# BMSNodeV1.net
KiCad netlist of a schematic drawn in EAGLE
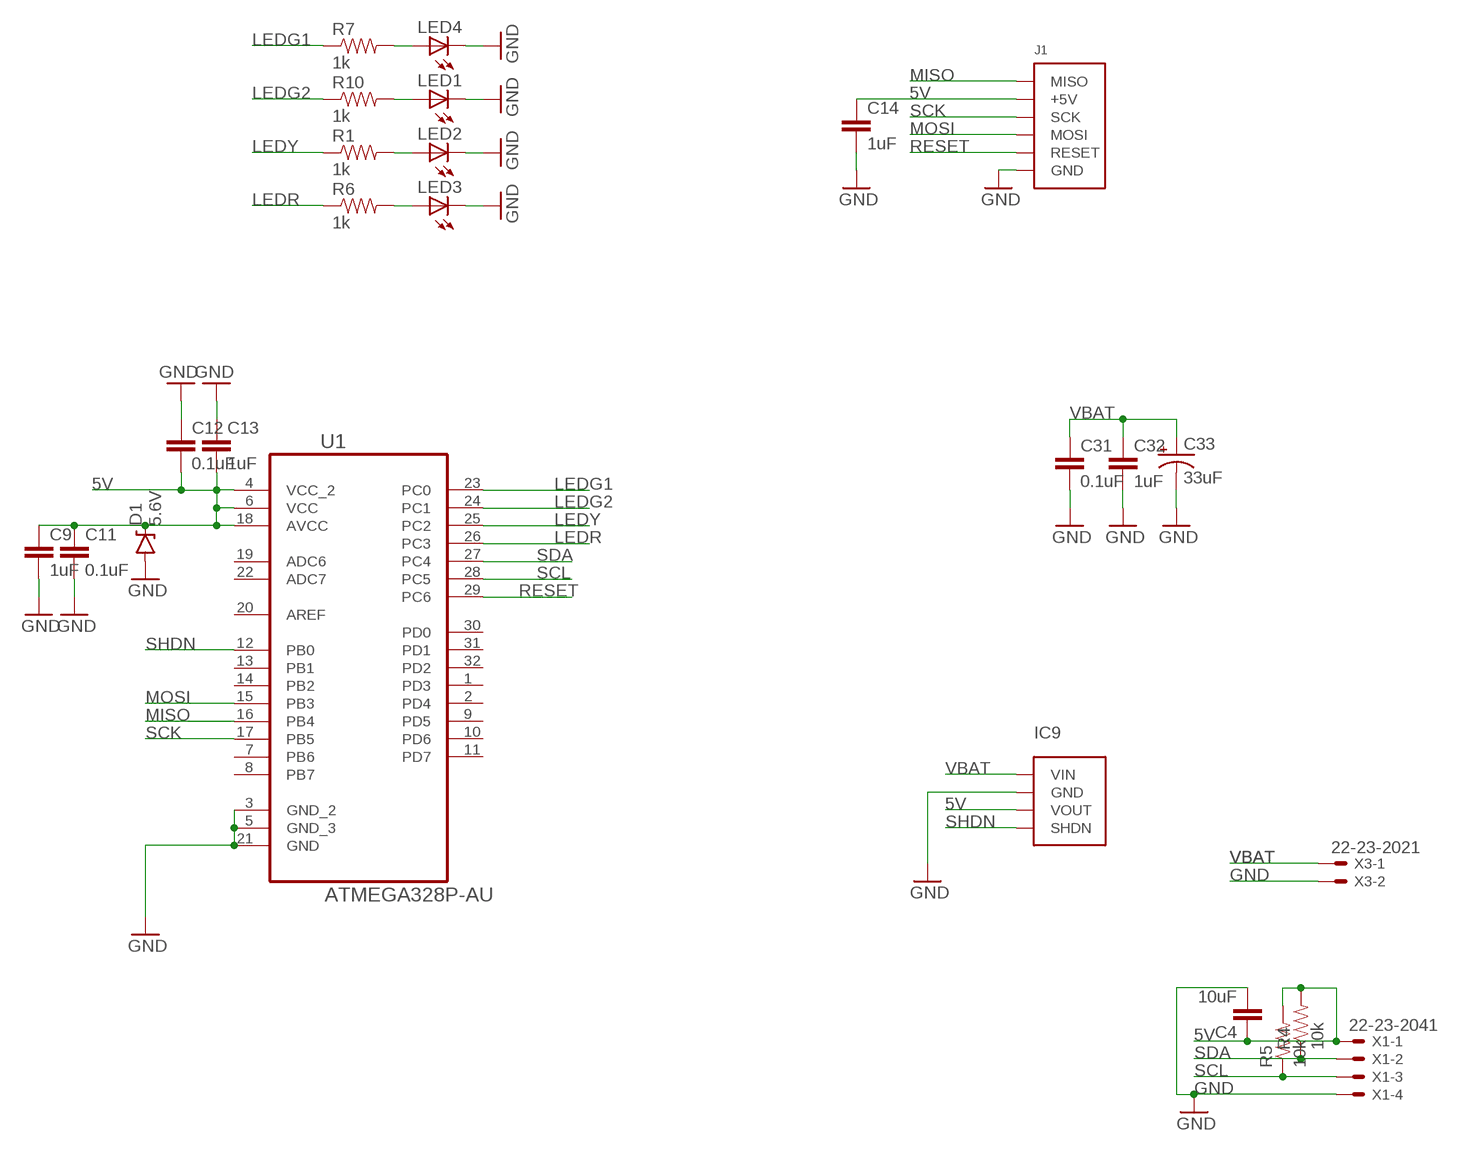
[diagram p0: schematic, sheet 1]

(export (version "E")
  (design (tool "Eeschema 10.0.6"))
  (components
    (comp (ref "C4")
      (value "10uF")
      (footprint "eagle-import:0805-CAP")
      (libsource (lib "eagle-import") (part "10UF10V10%(0805)"))
    )
    (comp (ref "C9")
      (value "1uF")
      (footprint "eagle-import:0805-CAP")
      (libsource (lib "eagle-import") (part "0.33UF-50V-10%(0805)"))
    )
    (comp (ref "C11")
      (value "0.1uF")
      (footprint "eagle-import:0805-CAP")
      (libsource (lib "eagle-import") (part "0.33UF-50V-10%(0805)"))
    )
    (comp (ref "C12")
      (value "0.1uF")
      (footprint "eagle-import:0805-CAP")
      (libsource (lib "eagle-import") (part "0.33UF-50V-10%(0805)"))
    )
    (comp (ref "C13")
      (value "1uF")
      (footprint "eagle-import:0805-CAP")
      (libsource (lib "eagle-import") (part "0.33UF-50V-10%(0805)"))
    )
    (comp (ref "C14")
      (value "1uF")
      (footprint "eagle-import:0805-CAP")
      (libsource (lib "eagle-import") (part "0.33UF-50V-10%(0805)"))
    )
    (comp (ref "C31")
      (value "0.1uF")
      (footprint "eagle-import:0805-CAP")
      (libsource (lib "eagle-import") (part "0.33UF-50V-10%(0805)"))
    )
    (comp (ref "C32")
      (value "1uF")
      (footprint "eagle-import:0805-CAP")
      (libsource (lib "eagle-import") (part "0.33UF-50V-10%(0805)"))
    )
    (comp (ref "C33")
      (value "33uF")
      (footprint "eagle-import:NIPPON_F80")
      (libsource (lib "eagle-import") (part "CAP_POLF80"))
    )
    (comp (ref "D1")
      (value "5.6V")
      (footprint "eagle-import:SOD-323")
      (libsource (lib "eagle-import") (part "DIODE-ZENER5.6V"))
    )
    (comp (ref "IC9")
      (value "5VBUCK_DANNY_CUSTOM_PCB")
      (footprint "eagle-import:4PIN_.1'")
      (libsource (lib "eagle-import") (part "5VBUCK_DANNY_CUSTOM_PCB"))
    )
    (comp (ref "J1")
      (value "ISPHEADER")
      (footprint "eagle-import:2X3PIN_.1'")
      (libsource (lib "eagle-import") (part "ISPHEADER"))
    )
    (comp (ref "LED1")
      (value "LEDCHIPLED_0805")
      (footprint "eagle-import:CHIPLED_0805")
      (libsource (lib "eagle-import") (part "LEDCHIPLED_0805"))
    )
    (comp (ref "LED2")
      (value "LEDCHIPLED_0805")
      (footprint "eagle-import:CHIPLED_0805")
      (libsource (lib "eagle-import") (part "LEDCHIPLED_0805"))
    )
    (comp (ref "LED3")
      (value "LEDCHIPLED_0805")
      (footprint "eagle-import:CHIPLED_0805")
      (libsource (lib "eagle-import") (part "LEDCHIPLED_0805"))
    )
    (comp (ref "LED4")
      (value "LEDCHIPLED_0805")
      (footprint "eagle-import:CHIPLED_0805")
      (libsource (lib "eagle-import") (part "LEDCHIPLED_0805"))
    )
    (comp (ref "R1")
      (value "1k")
      (footprint "eagle-import:0805")
      (libsource (lib "eagle-import") (part "0.3OHM-1/8W-1%(0805)"))
    )
    (comp (ref "R4")
      (value "10k")
      (footprint "eagle-import:0805")
      (libsource (lib "eagle-import") (part "0.3OHM-1/8W-1%(0805)"))
    )
    (comp (ref "R5")
      (value "10k")
      (footprint "eagle-import:0805")
      (libsource (lib "eagle-import") (part "0.3OHM-1/8W-1%(0805)"))
    )
    (comp (ref "R6")
      (value "1k")
      (footprint "eagle-import:0805")
      (libsource (lib "eagle-import") (part "0.3OHM-1/8W-1%(0805)"))
    )
    (comp (ref "R7")
      (value "1k")
      (footprint "eagle-import:0805")
      (libsource (lib "eagle-import") (part "0.3OHM-1/8W-1%(0805)"))
    )
    (comp (ref "R10")
      (value "1k")
      (footprint "eagle-import:0805")
      (libsource (lib "eagle-import") (part "0.3OHM-1/8W-1%(0805)"))
    )
    (comp (ref "U1")
      (value "ATMEGA328P-AU")
      (footprint "eagle-import:QFP80P900X900X120-32N")
      (libsource (lib "eagle-import") (part "ATMEGA328P-AU"))
    )
    (comp (ref "X1")
      (value "22-23-2041")
      (footprint "eagle-import:22-23-2041")
      (fields (field (name "MF") "MOLEX"))
      (libsource (lib "eagle-import") (part "22-23-2041"))
    )
    (comp (ref "X3")
      (value "22-23-2021")
      (footprint "eagle-import:22-23-2021")
      (fields (field (name "MF") "MOLEX"))
      (libsource (lib "eagle-import") (part "22-23-2021"))
    )
  )
  (nets
    (net (code "1") (name "/5V") (class "Default")
      (node (ref "C11") (pin "1") (pinfunction "1_1") (pintype "passive"))
      (node (ref "C12") (pin "2") (pinfunction "2_2") (pintype "passive"))
      (node (ref "C13") (pin "2") (pinfunction "2_2") (pintype "passive"))
      (node (ref "C14") (pin "1") (pinfunction "1_1") (pintype "passive"))
      (node (ref "C4") (pin "1") (pinfunction "1_1") (pintype "passive"))
      (node (ref "C9") (pin "1") (pinfunction "1_1") (pintype "passive"))
      (node (ref "D1") (pin "C") (pinfunction "C_C") (pintype "passive"))
      (node (ref "IC9") (pin "P$3") (pinfunction "VOUT_P$3") (pintype "bidirectional"))
      (node (ref "J1") (pin "P$2") (pinfunction "+5V_P$2") (pintype "bidirectional"))
      (node (ref "R4") (pin "2") (pinfunction "2_2") (pintype "passive"))
      (node (ref "R5") (pin "2") (pinfunction "2_2") (pintype "passive"))
      (node (ref "U1") (pin "18") (pinfunction "AVCC_18") (pintype "power_in"))
      (node (ref "U1") (pin "4") (pinfunction "VCC_2_4") (pintype "power_in"))
      (node (ref "U1") (pin "6") (pinfunction "VCC_6") (pintype "power_in"))
      (node (ref "X1") (pin "1") (pinfunction "S_1") (pintype "passive"))
    )
    (net (code "2") (name "/LEDG1") (class "Default")
      (node (ref "R7") (pin "1") (pinfunction "1_1") (pintype "passive"))
      (node (ref "U1") (pin "23") (pinfunction "PC0_23") (pintype "bidirectional"))
    )
    (net (code "3") (name "/LEDG2") (class "Default")
      (node (ref "R10") (pin "1") (pinfunction "1_1") (pintype "passive"))
      (node (ref "U1") (pin "24") (pinfunction "PC1_24") (pintype "bidirectional"))
    )
    (net (code "4") (name "/LEDR") (class "Default")
      (node (ref "R6") (pin "1") (pinfunction "1_1") (pintype "passive"))
      (node (ref "U1") (pin "26") (pinfunction "PC3_26") (pintype "bidirectional"))
    )
    (net (code "5") (name "/LEDY") (class "Default")
      (node (ref "R1") (pin "1") (pinfunction "1_1") (pintype "passive"))
      (node (ref "U1") (pin "25") (pinfunction "PC2_25") (pintype "bidirectional"))
    )
    (net (code "6") (name "/MISO") (class "Default")
      (node (ref "J1") (pin "P$1") (pinfunction "MISO_P$1") (pintype "bidirectional"))
      (node (ref "U1") (pin "16") (pinfunction "PB4_16") (pintype "bidirectional"))
    )
    (net (code "7") (name "/MOSI") (class "Default")
      (node (ref "J1") (pin "P$4") (pinfunction "MOSI_P$4") (pintype "bidirectional"))
      (node (ref "U1") (pin "15") (pinfunction "PB3_15") (pintype "bidirectional"))
    )
    (net (code "8") (name "/RESET") (class "Default")
      (node (ref "J1") (pin "P$5") (pinfunction "RESET_P$5") (pintype "bidirectional"))
      (node (ref "U1") (pin "29") (pinfunction "PC6_29") (pintype "bidirectional"))
    )
    (net (code "9") (name "/SCK") (class "Default")
      (node (ref "J1") (pin "P$3") (pinfunction "SCK_P$3") (pintype "bidirectional"))
      (node (ref "U1") (pin "17") (pinfunction "PB5_17") (pintype "bidirectional"))
    )
    (net (code "10") (name "/SCL") (class "Default")
      (node (ref "R5") (pin "1") (pinfunction "1_1") (pintype "passive"))
      (node (ref "U1") (pin "28") (pinfunction "PC5_28") (pintype "bidirectional"))
      (node (ref "X1") (pin "3") (pinfunction "S_3") (pintype "passive"))
    )
    (net (code "11") (name "/SDA") (class "Default")
      (node (ref "R4") (pin "1") (pinfunction "1_1") (pintype "passive"))
      (node (ref "U1") (pin "27") (pinfunction "PC4_27") (pintype "bidirectional"))
      (node (ref "X1") (pin "2") (pinfunction "S_2") (pintype "passive"))
    )
    (net (code "12") (name "/SHDN") (class "Default")
      (node (ref "IC9") (pin "P$4") (pinfunction "SHDN_P$4") (pintype "bidirectional"))
      (node (ref "U1") (pin "12") (pinfunction "PB0_12") (pintype "bidirectional"))
    )
    (net (code "13") (name "/VBAT") (class "Default")
      (node (ref "C31") (pin "1") (pinfunction "1_1") (pintype "passive"))
      (node (ref "C32") (pin "1") (pinfunction "1_1") (pintype "passive"))
      (node (ref "C33") (pin "+") (pinfunction "+_+") (pintype "passive"))
      (node (ref "IC9") (pin "P$1") (pinfunction "VIN_P$1") (pintype "bidirectional"))
      (node (ref "X3") (pin "1") (pinfunction "S_1") (pintype "passive"))
    )
    (net (code "14") (name "GND") (class "Default")
      (node (ref "C11") (pin "2") (pinfunction "2_2") (pintype "passive"))
      (node (ref "C12") (pin "1") (pinfunction "1_1") (pintype "passive"))
      (node (ref "C13") (pin "1") (pinfunction "1_1") (pintype "passive"))
      (node (ref "C14") (pin "2") (pinfunction "2_2") (pintype "passive"))
      (node (ref "C31") (pin "2") (pinfunction "2_2") (pintype "passive"))
      (node (ref "C32") (pin "2") (pinfunction "2_2") (pintype "passive"))
      (node (ref "C33") (pin "-") (pinfunction "-_-") (pintype "passive"))
      (node (ref "C4") (pin "2") (pinfunction "2_2") (pintype "passive"))
      (node (ref "C9") (pin "2") (pinfunction "2_2") (pintype "passive"))
      (node (ref "D1") (pin "A") (pinfunction "A_A") (pintype "passive"))
      (node (ref "IC9") (pin "P$2") (pinfunction "GND_P$2") (pintype "bidirectional"))
      (node (ref "J1") (pin "P$6") (pinfunction "GND_P$6") (pintype "bidirectional"))
      (node (ref "LED1") (pin "C") (pinfunction "C_C") (pintype "passive"))
      (node (ref "LED2") (pin "C") (pinfunction "C_C") (pintype "passive"))
      (node (ref "LED3") (pin "C") (pinfunction "C_C") (pintype "passive"))
      (node (ref "LED4") (pin "C") (pinfunction "C_C") (pintype "passive"))
      (node (ref "U1") (pin "21") (pinfunction "GND_21") (pintype "passive"))
      (node (ref "U1") (pin "3") (pinfunction "GND_2_3") (pintype "passive"))
      (node (ref "U1") (pin "5") (pinfunction "GND_3_5") (pintype "passive"))
      (node (ref "X1") (pin "4") (pinfunction "S_4") (pintype "passive"))
      (node (ref "X3") (pin "2") (pinfunction "S_2") (pintype "passive"))
    )
    (net (code "15") (name "Net-(LED1-PadA)") (class "Default")
      (node (ref "LED1") (pin "A") (pinfunction "A_A") (pintype "passive"))
      (node (ref "R10") (pin "2") (pinfunction "2_2") (pintype "passive"))
    )
    (net (code "16") (name "Net-(LED2-PadA)") (class "Default")
      (node (ref "LED2") (pin "A") (pinfunction "A_A") (pintype "passive"))
      (node (ref "R1") (pin "2") (pinfunction "2_2") (pintype "passive"))
    )
    (net (code "17") (name "Net-(LED3-PadA)") (class "Default")
      (node (ref "LED3") (pin "A") (pinfunction "A_A") (pintype "passive"))
      (node (ref "R6") (pin "2") (pinfunction "2_2") (pintype "passive"))
    )
    (net (code "18") (name "Net-(LED4-PadA)") (class "Default")
      (node (ref "LED4") (pin "A") (pinfunction "A_A") (pintype "passive"))
      (node (ref "R7") (pin "2") (pinfunction "2_2") (pintype "passive"))
    )
    (net (code "19") (name "unconnected-(U1-ADC6-Pad19)") (class "Default")
      (node (ref "U1") (pin "19") (pinfunction "ADC6_19") (pintype "input"))
    )
    (net (code "20") (name "unconnected-(U1-ADC7-Pad22)") (class "Default")
      (node (ref "U1") (pin "22") (pinfunction "ADC7_22") (pintype "input"))
    )
    (net (code "21") (name "unconnected-(U1-AREF-Pad20)") (class "Default")
      (node (ref "U1") (pin "20") (pinfunction "AREF_20") (pintype "input"))
    )
    (net (code "22") (name "unconnected-(U1-PB1-Pad13)") (class "Default")
      (node (ref "U1") (pin "13") (pinfunction "PB1_13") (pintype "bidirectional"))
    )
    (net (code "23") (name "unconnected-(U1-PB2-Pad14)") (class "Default")
      (node (ref "U1") (pin "14") (pinfunction "PB2_14") (pintype "bidirectional"))
    )
    (net (code "24") (name "unconnected-(U1-PB6-Pad7)") (class "Default")
      (node (ref "U1") (pin "7") (pinfunction "PB6_7") (pintype "bidirectional"))
    )
    (net (code "25") (name "unconnected-(U1-PB7-Pad8)") (class "Default")
      (node (ref "U1") (pin "8") (pinfunction "PB7_8") (pintype "bidirectional"))
    )
    (net (code "26") (name "unconnected-(U1-PD0-Pad30)") (class "Default")
      (node (ref "U1") (pin "30") (pinfunction "PD0_30") (pintype "bidirectional"))
    )
    (net (code "27") (name "unconnected-(U1-PD1-Pad31)") (class "Default")
      (node (ref "U1") (pin "31") (pinfunction "PD1_31") (pintype "bidirectional"))
    )
    (net (code "28") (name "unconnected-(U1-PD2-Pad32)") (class "Default")
      (node (ref "U1") (pin "32") (pinfunction "PD2_32") (pintype "bidirectional"))
    )
    (net (code "29") (name "unconnected-(U1-PD3-Pad1)") (class "Default")
      (node (ref "U1") (pin "1") (pinfunction "PD3_1") (pintype "bidirectional"))
    )
    (net (code "30") (name "unconnected-(U1-PD4-Pad2)") (class "Default")
      (node (ref "U1") (pin "2") (pinfunction "PD4_2") (pintype "bidirectional"))
    )
    (net (code "31") (name "unconnected-(U1-PD5-Pad9)") (class "Default")
      (node (ref "U1") (pin "9") (pinfunction "PD5_9") (pintype "bidirectional"))
    )
    (net (code "32") (name "unconnected-(U1-PD6-Pad10)") (class "Default")
      (node (ref "U1") (pin "10") (pinfunction "PD6_10") (pintype "bidirectional"))
    )
    (net (code "33") (name "unconnected-(U1-PD7-Pad11)") (class "Default")
      (node (ref "U1") (pin "11") (pinfunction "PD7_11") (pintype "bidirectional"))
    )
  )
)
